# schema_carte_US.net
KiCad netlist of a schematic drawn in EAGLE
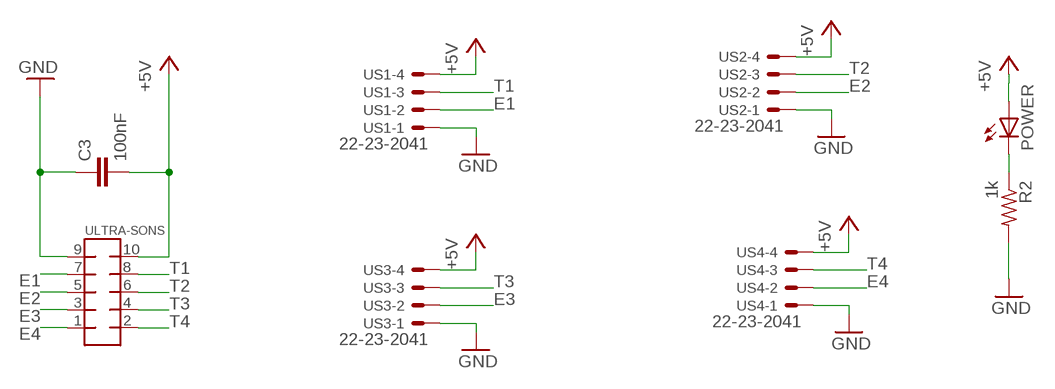
[diagram p0: schematic, sheet 1]

(export (version "E")
  (design (tool "Eeschema 10.0.6"))
  (components
    (comp (ref "C3")
      (value "100nF")
      (footprint "eagle-import:C0805")
      (libsource (lib "eagle-import") (part "C-EUC0805"))
    )
    (comp (ref "POWER")
      (value "LEDCHIPLED_0805")
      (footprint "eagle-import:CHIPLED_0805")
      (libsource (lib "eagle-import") (part "LEDCHIPLED_0805"))
    )
    (comp (ref "R2")
      (value "1k")
      (footprint "eagle-import:M0805")
      (libsource (lib "eagle-import") (part "R-US_M0805"))
    )
    (comp (ref "ULTRA-SONS")
      (value "MMATCH-10-PTH")
      (footprint "eagle-import:AMP-215079-10")
      (libsource (lib "eagle-import") (part "MMATCH-10-PTH"))
    )
    (comp (ref "US1")
      (value "22-23-2041")
      (footprint "eagle-import:22-23-2041")
      (fields (field (name "MF") "MOLEX"))
      (libsource (lib "eagle-import") (part "22-23-2041"))
    )
    (comp (ref "US2")
      (value "22-23-2041")
      (footprint "eagle-import:22-23-2041")
      (fields (field (name "MF") "MOLEX"))
      (libsource (lib "eagle-import") (part "22-23-2041"))
    )
    (comp (ref "US3")
      (value "22-23-2041")
      (footprint "eagle-import:22-23-2041")
      (fields (field (name "MF") "MOLEX"))
      (libsource (lib "eagle-import") (part "22-23-2041"))
    )
    (comp (ref "US4")
      (value "22-23-2041")
      (footprint "eagle-import:22-23-2041")
      (fields (field (name "MF") "MOLEX"))
      (libsource (lib "eagle-import") (part "22-23-2041"))
    )
  )
  (nets
    (net (code "1") (name "+5V") (class "Default")
      (node (ref "C3") (pin "2") (pinfunction "2_2") (pintype "passive"))
      (node (ref "POWER") (pin "A") (pinfunction "A_A") (pintype "passive"))
      (node (ref "ULTRA-SONS") (pin "10") (pinfunction "10_10") (pintype "bidirectional"))
      (node (ref "US1") (pin "4") (pinfunction "S_4") (pintype "passive"))
      (node (ref "US2") (pin "4") (pinfunction "S_4") (pintype "passive"))
      (node (ref "US3") (pin "4") (pinfunction "S_4") (pintype "passive"))
      (node (ref "US4") (pin "4") (pinfunction "S_4") (pintype "passive"))
    )
    (net (code "2") (name "/E1") (class "Default")
      (node (ref "ULTRA-SONS") (pin "7") (pinfunction "7_7") (pintype "bidirectional"))
      (node (ref "US1") (pin "2") (pinfunction "S_2") (pintype "passive"))
    )
    (net (code "3") (name "/E2") (class "Default")
      (node (ref "ULTRA-SONS") (pin "5") (pinfunction "5_5") (pintype "bidirectional"))
      (node (ref "US2") (pin "2") (pinfunction "S_2") (pintype "passive"))
    )
    (net (code "4") (name "/E3") (class "Default")
      (node (ref "ULTRA-SONS") (pin "3") (pinfunction "3_3") (pintype "bidirectional"))
      (node (ref "US3") (pin "2") (pinfunction "S_2") (pintype "passive"))
    )
    (net (code "5") (name "/E4") (class "Default")
      (node (ref "ULTRA-SONS") (pin "1") (pinfunction "1_1") (pintype "bidirectional"))
      (node (ref "US4") (pin "2") (pinfunction "S_2") (pintype "passive"))
    )
    (net (code "6") (name "/T1") (class "Default")
      (node (ref "ULTRA-SONS") (pin "8") (pinfunction "8_8") (pintype "bidirectional"))
      (node (ref "US1") (pin "3") (pinfunction "S_3") (pintype "passive"))
    )
    (net (code "7") (name "/T2") (class "Default")
      (node (ref "ULTRA-SONS") (pin "6") (pinfunction "6_6") (pintype "bidirectional"))
      (node (ref "US2") (pin "3") (pinfunction "S_3") (pintype "passive"))
    )
    (net (code "8") (name "/T3") (class "Default")
      (node (ref "ULTRA-SONS") (pin "4") (pinfunction "4_4") (pintype "bidirectional"))
      (node (ref "US3") (pin "3") (pinfunction "S_3") (pintype "passive"))
    )
    (net (code "9") (name "/T4") (class "Default")
      (node (ref "ULTRA-SONS") (pin "2") (pinfunction "2_2") (pintype "bidirectional"))
      (node (ref "US4") (pin "3") (pinfunction "S_3") (pintype "passive"))
    )
    (net (code "10") (name "GND") (class "Default")
      (node (ref "C3") (pin "1") (pinfunction "1_1") (pintype "passive"))
      (node (ref "R2") (pin "2") (pinfunction "2_2") (pintype "passive"))
      (node (ref "ULTRA-SONS") (pin "9") (pinfunction "9_9") (pintype "bidirectional"))
      (node (ref "US1") (pin "1") (pinfunction "S_1") (pintype "passive"))
      (node (ref "US2") (pin "1") (pinfunction "S_1") (pintype "passive"))
      (node (ref "US3") (pin "1") (pinfunction "S_1") (pintype "passive"))
      (node (ref "US4") (pin "1") (pinfunction "S_1") (pintype "passive"))
    )
    (net (code "11") (name "Net-(POWER-PadC)") (class "Default")
      (node (ref "POWER") (pin "C") (pinfunction "C_C") (pintype "passive"))
      (node (ref "R2") (pin "1") (pinfunction "1_1") (pintype "passive"))
    )
  )
)
